# Main_Power_Switch.net
KiCad netlist of a schematic drawn in Altium Designer
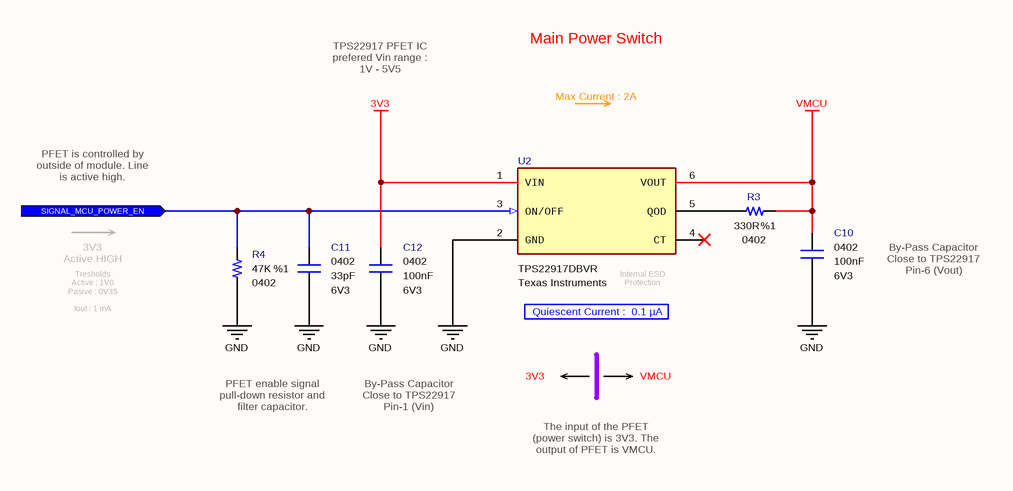
[diagram p0: Main Power Switch.SchDoc]

(export (version "E")
  (design (tool "Eeschema 10.0.6"))
  (components
    (comp (ref "C10")
      (value "100nF")
      (footprint "CAPACITOR_0402")
      (description "Capacitor - 100nF [0402-6V3] (Ceramic)")
      (fields
        (field (name "TOLERANCE") "%10")
        (field (name "CASE") "0402")
        (field (name "VOLTAGE") "6V3")
        (field (name "MANUFACTURER PART NUMBER") "04026D104KAT4A")
      )
      (libsource (lib "Ovoo_Library") (part "Capacitor - 100nF [0402-6V3]"))
    )
    (comp (ref "C11")
      (value "33pF")
      (footprint "CAPACITOR_0402")
      (description "Capacitor - 33pF [0402] (Ceramic)")
      (fields
        (field (name "TOLERANCE") "10%")
        (field (name "CASE") "0402")
        (field (name "VOLTAGE") "6V3")
        (field (name "MANUFACTURER PART NUMBER") "C0402C330J9RACAUTO")
      )
      (libsource (lib "Ovoo_Library") (part "Capacitor - 33pF [0402-6V3]"))
    )
    (comp (ref "C12")
      (value "100nF")
      (footprint "CAPACITOR_0402")
      (description "Capacitor - 100nF [0402-6V3] (Ceramic)")
      (fields
        (field (name "CASE") "0402")
        (field (name "TOLERANCE") "%10")
        (field (name "VOLTAGE") "6V3")
        (field (name "MANUFACTURER PART NUMBER") "04026D104KAT4A")
      )
      (libsource (lib "Ovoo_Library") (part "Capacitor - 100nF [0402-6V3]"))
    )
    (comp (ref "R3")
      (value "330R")
      (footprint "RESISTOR_0402")
      (description "Thick Film Resistors - SMD 1/16 W 330 Ohm 1%")
      (fields
        (field (name "TOLERANCE") "%1")
        (field (name "CASE") "0402")
        (field (name "MANUFACTURER PART NUMBER") "CRCW0402330RFKED")
        (field (name "MOUSER PART NUMBER") "71-CRCW0402-330-E3")
      )
      (libsource (lib "Ovoo_Library") (part "Resistor - 330R"))
    )
    (comp (ref "R4")
      (value "47K")
      (footprint "RESISTOR_0402")
      (description "Thick Film Resistors - SMD 1/16 W 47 Kohms 1%")
      (fields
        (field (name "TOLERANCE") "%1")
        (field (name "CASE") "0402")
        (field (name "MANUFACTURER PART NUMBER") "CRCW040247K0FKED")
        (field (name "MOUSER PART NUMBER") "71-CRCW0402-47K-E3")
      )
      (libsource (lib "Ovoo_Library") (part "Resistor - 47K"))
    )
    (comp (ref "U2")
      (value "Power Switch")
      (footprint "SOT-23-6")
      (description "Power Switch MosFet")
      (fields
        (field (name "MOUSER PART NUMBER") "595-TPS22917DBVR")
        (field (name "MANUFACTURER PART NUMBER") "TPS22917DBVR")
        (field (name "MANUFACTURER NAME") "Texas Instruments")
      )
      (libsource (lib "Ovoo_Library") (part "IC - TPS22917DBVR"))
    )
  )
  (nets
    (net (code "1") (name "/SIGNAL_MCU_POWER_EN") (class "Default")
      (node (ref "C11") (pin "2") (pinfunction "2_2") (pintype "passive"))
      (node (ref "R4") (pin "2") (pinfunction "2_2") (pintype "passive"))
      (node (ref "U2") (pin "3") (pinfunction "ON/OFF_3") (pintype "input"))
    )
    (net (code "2") (name "3V3") (class "Default")
      (node (ref "C12") (pin "1") (pinfunction "1_1") (pintype "passive"))
      (node (ref "U2") (pin "1") (pinfunction "VIN_1") (pintype "power_in"))
    )
    (net (code "3") (name "GND") (class "Default")
      (node (ref "C10") (pin "2") (pinfunction "2_2") (pintype "passive"))
      (node (ref "C11") (pin "1") (pinfunction "1_1") (pintype "passive"))
      (node (ref "C12") (pin "2") (pinfunction "2_2") (pintype "passive"))
      (node (ref "R4") (pin "1") (pinfunction "1_1") (pintype "passive"))
      (node (ref "U2") (pin "2") (pinfunction "GND_2") (pintype "power_in"))
    )
    (net (code "4") (name "Net-(U2-QOD)") (class "Default")
      (node (ref "R3") (pin "2") (pinfunction "2_2") (pintype "passive"))
      (node (ref "U2") (pin "5") (pinfunction "QOD_5") (pintype "power_in"))
    )
    (net (code "5") (name "VMCU") (class "Default")
      (node (ref "C10") (pin "1") (pinfunction "1_1") (pintype "passive"))
      (node (ref "R3") (pin "1") (pinfunction "1_1") (pintype "passive"))
      (node (ref "U2") (pin "6") (pinfunction "VOUT_6") (pintype "power_in"))
    )
    (net (code "6") (name "unconnected-(U2-CT-Pad4)") (class "Default")
      (node (ref "U2") (pin "4") (pinfunction "CT_4") (pintype "power_in+no_connect"))
    )
  )
)
